# Main.net
KiCad netlist of a schematic drawn in Altium Designer
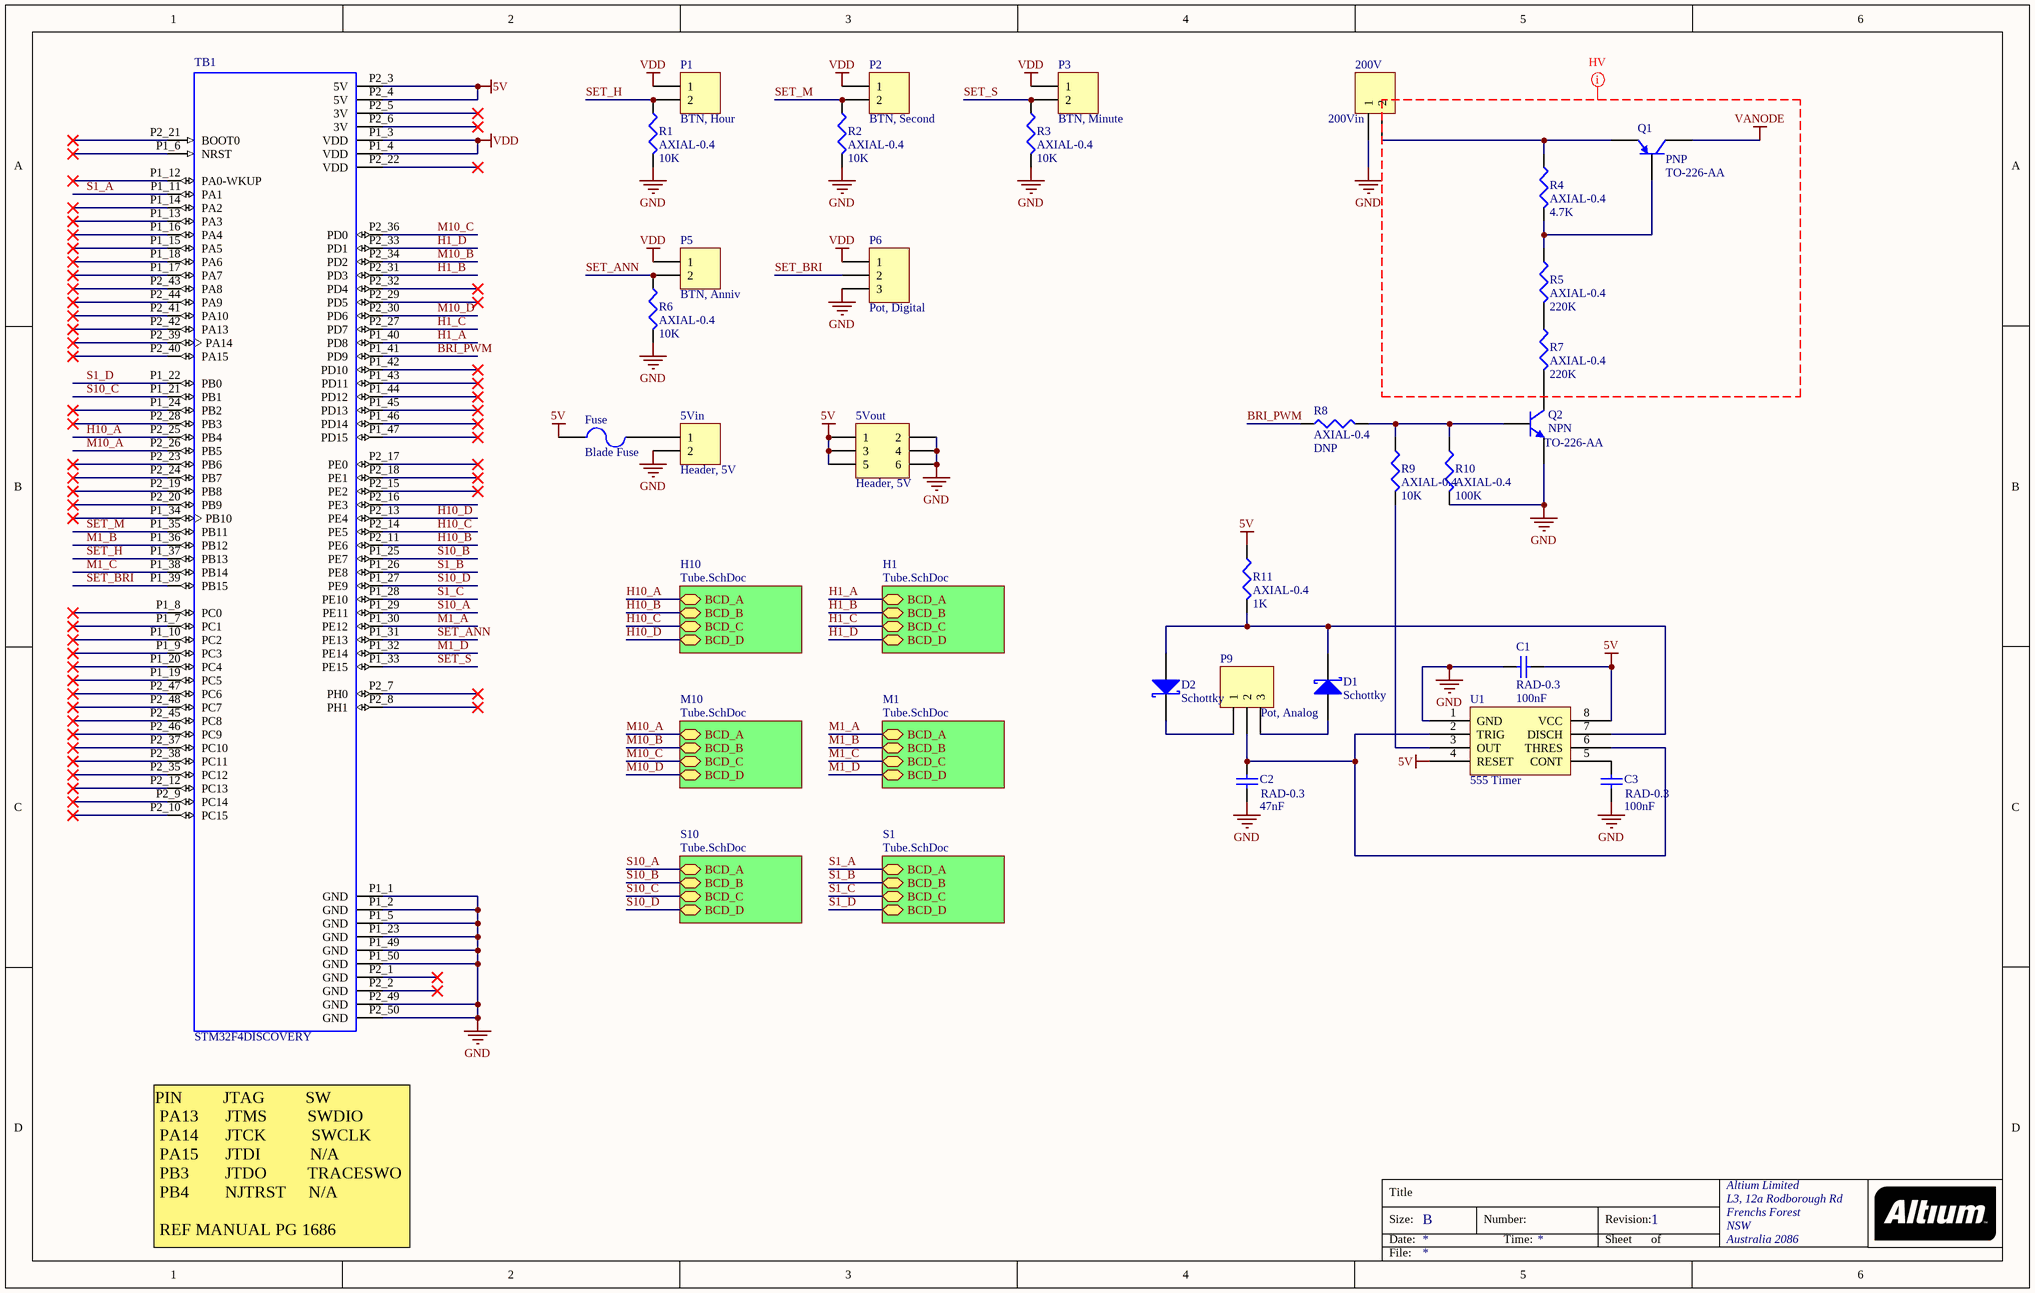
[diagram p0: Main.SchDoc]

(export (version "E")
  (design (tool "Eeschema 10.0.6"))
  (components
    (comp (ref "5Vin")
      (value "Header, 5V")
      (footprint "HDR1X2")
      (description "Header, 2-Pin")
      (fields (field (name "PUBLISHER") "Altium Limited"))
      (libsource (lib "Miscellaneous Connectors") (part "Header 2"))
    )
    (comp (ref "5Vout")
      (value "Header, 5V")
      (footprint "HDR2X3")
      (description "Header, 3-Pin, Dual row")
      (fields (field (name "PUBLISHER") "Altium Limited"))
      (libsource (lib "Miscellaneous Connectors") (part "Header 3X2"))
    )
    (comp (ref "200V")
      (value "200Vin")
      (footprint "HDR1X2H")
      (description "Header, 2-Pin, Right Angle")
      (fields (field (name "PUBLISHER") "Altium Limited"))
      (libsource (lib "Miscellaneous Connectors") (part "Header 2H"))
    )
    (comp (ref "C1")
      (value "100nF")
      (footprint "RAD-0.3")
      (description "Capacitor")
      (fields
        (field (name "PACKAGEREFERENCE") "RAD-0.3")
        (field (name "Comment") "Cap")
        (field (name "PUBLISHER") "Altium Limited")
      )
      (libsource (lib "Miscellaneous Devices") (part "Cap"))
    )
    (comp (ref "C2")
      (value "47nF")
      (footprint "RAD-0.3")
      (description "Capacitor")
      (fields (field (name "PACKAGEREFERENCE") "RAD-0.3") (field (name "PUBLISHER") "Altium Limited"))
      (libsource (lib "Miscellaneous Devices") (part "Cap"))
    )
    (comp (ref "C3")
      (value "100nF")
      (footprint "RAD-0.3")
      (description "Capacitor")
      (fields
        (field (name "PACKAGEREFERENCE") "RAD-0.3")
        (field (name "Comment") "Cap")
        (field (name "PUBLISHER") "Altium Limited")
      )
      (libsource (lib "Miscellaneous Devices") (part "Cap"))
    )
    (comp (ref "D1")
      (value "Schottky")
      (footprint "AXIAL-0.4")
      (description "Schottky Diode")
      (fields (field (name "PUBLISHER") "Altium Limited"))
      (libsource (lib "Miscellaneous Devices") (part "D Schottky"))
    )
    (comp (ref "D2")
      (value "Schottky")
      (footprint "AXIAL-0.4")
      (description "Schottky Diode")
      (fields (field (name "PUBLISHER") "Altium Limited"))
      (libsource (lib "Miscellaneous Devices") (part "D Schottky"))
    )
    (comp (ref "Fuse")
      (value "Blade Fuse")
      (footprint "FUSEHOLDER")
      (description "Fuse")
      (fields (field (name "PUBLISHER") "Altium Limited"))
      (libsource (lib "Miscellaneous Devices") (part "Fuse 2"))
    )
    (comp (ref "P1")
      (value "BTN, Hour")
      (footprint "HDR1X2")
      (description "Header, 2-Pin")
      (fields (field (name "PUBLISHER") "Altium Limited"))
      (libsource (lib "Miscellaneous Connectors") (part "Header 2"))
    )
    (comp (ref "P2")
      (value "BTN, Second")
      (footprint "HDR1X2")
      (description "Header, 2-Pin")
      (fields (field (name "PUBLISHER") "Altium Limited"))
      (libsource (lib "Miscellaneous Connectors") (part "Header 2"))
    )
    (comp (ref "P3")
      (value "BTN, Minute")
      (footprint "HDR1X2")
      (description "Header, 2-Pin")
      (fields (field (name "PUBLISHER") "Altium Limited"))
      (libsource (lib "Miscellaneous Connectors") (part "Header 2"))
    )
    (comp (ref "P5")
      (value "BTN, Anniv")
      (footprint "HDR1X2")
      (description "Header, 2-Pin")
      (fields (field (name "PUBLISHER") "Altium Limited"))
      (libsource (lib "Miscellaneous Connectors") (part "Header 2"))
    )
    (comp (ref "P6")
      (value "Pot, Digital")
      (footprint "HDR1X3")
      (description "Header, 3-Pin")
      (fields (field (name "PUBLISHER") "Altium Limited"))
      (libsource (lib "") (part "Header 3_1"))
    )
    (comp (ref "P9")
      (value "Pot, Analog")
      (footprint "HDR1X3")
      (description "Header, 3-Pin")
      (fields (field (name "PUBLISHER") "Altium Limited"))
      (libsource (lib "Miscellaneous Connectors") (part "Header 3"))
    )
    (comp (ref "Q1")
      (value "PNP")
      (footprint "T0-226-BEND")
      (description "PNP Bipolar Transistor")
      (fields (field (name "PACKAGEREFERENCE") "TO-226-AA") (field (name "PUBLISHER") "Altium Limited"))
      (libsource (lib "Miscellaneous Devices") (part "PNP"))
    )
    (comp (ref "Q2")
      (value "NPN")
      (footprint "T0-226-BEND")
      (description "NPN Bipolar Transistor")
      (fields (field (name "PACKAGEREFERENCE") "TO-226-AA") (field (name "PUBLISHER") "Altium Limited"))
      (libsource (lib "Miscellaneous Devices") (part "NPN"))
    )
    (comp (ref "R1")
      (value "AXIAL-0.4")
      (footprint "AXIAL-0.4")
      (description "Resistor")
      (fields (field (name "ALTIUM_VALUE") "10K") (field (name "PUBLISHER") "Altium Limited"))
      (libsource (lib "Miscellaneous Devices") (part "Res3"))
    )
    (comp (ref "R2")
      (value "AXIAL-0.4")
      (footprint "AXIAL-0.4")
      (description "Resistor")
      (fields (field (name "ALTIUM_VALUE") "10K") (field (name "PUBLISHER") "Altium Limited"))
      (libsource (lib "Miscellaneous Devices") (part "Res3"))
    )
    (comp (ref "R3")
      (value "AXIAL-0.4")
      (footprint "AXIAL-0.4")
      (description "Resistor")
      (fields (field (name "ALTIUM_VALUE") "10K") (field (name "PUBLISHER") "Altium Limited"))
      (libsource (lib "Miscellaneous Devices") (part "Res3"))
    )
    (comp (ref "R4")
      (value "AXIAL-0.4")
      (footprint "AXIAL-0.4")
      (description "Resistor")
      (fields (field (name "ALTIUM_VALUE") "4.7K") (field (name "PUBLISHER") "Altium Limited"))
      (libsource (lib "Miscellaneous Devices") (part "Res3"))
    )
    (comp (ref "R5")
      (value "AXIAL-0.4")
      (footprint "AXIAL-0.4")
      (description "Resistor")
      (fields (field (name "ALTIUM_VALUE") "220K") (field (name "PUBLISHER") "Altium Limited"))
      (libsource (lib "Miscellaneous Devices") (part "Res3"))
    )
    (comp (ref "R6")
      (value "AXIAL-0.4")
      (footprint "AXIAL-0.4")
      (description "Resistor")
      (fields (field (name "ALTIUM_VALUE") "10K") (field (name "PUBLISHER") "Altium Limited"))
      (libsource (lib "Miscellaneous Devices") (part "Res3"))
    )
    (comp (ref "R7")
      (value "AXIAL-0.4")
      (footprint "AXIAL-0.4")
      (description "Resistor")
      (fields (field (name "ALTIUM_VALUE") "220K") (field (name "PUBLISHER") "Altium Limited"))
      (libsource (lib "Miscellaneous Devices") (part "Res3"))
    )
    (comp (ref "R8")
      (value "AXIAL-0.4")
      (footprint "AXIAL-0.4")
      (description "Resistor")
      (fields (field (name "ALTIUM_VALUE") "DNP") (field (name "PUBLISHER") "Altium Limited"))
      (libsource (lib "Miscellaneous Devices") (part "Res3"))
    )
    (comp (ref "R9")
      (value "AXIAL-0.4")
      (footprint "AXIAL-0.4")
      (description "Resistor")
      (fields (field (name "ALTIUM_VALUE") "10K") (field (name "PUBLISHER") "Altium Limited"))
      (libsource (lib "Miscellaneous Devices") (part "Res3"))
    )
    (comp (ref "R10")
      (value "AXIAL-0.4")
      (footprint "AXIAL-0.4")
      (description "Resistor")
      (fields (field (name "ALTIUM_VALUE") "100K") (field (name "PUBLISHER") "Altium Limited"))
      (libsource (lib "Miscellaneous Devices") (part "Res3"))
    )
    (comp (ref "R11")
      (value "AXIAL-0.4")
      (footprint "AXIAL-0.4")
      (description "Resistor")
      (fields (field (name "ALTIUM_VALUE") "1K") (field (name "PUBLISHER") "Altium Limited"))
      (libsource (lib "Miscellaneous Devices") (part "Res3"))
    )
    (comp (ref "TB1")
      (value "STM32F4DISCOVERY")
      (footprint "*MODULE_STM32F4DISCOVERY_STM32F4DISCOVERY_Primary")
      (description "Development kit: ARM ST; pin strips, pin header; No.of")
      (fields (field (name "MF") "STMicroelectronics"))
      (libsource (lib "STM32F4DISCOVERY") (part "STM32F4DISCOVERY"))
    )
    (comp (ref "U1")
      (value "555 Timer")
      (footprint "DIP-8")
      (fields (field (name "PARTNUMBER") "NE555P"))
      (libsource (lib "Schematic_Components") (part "555 Timer"))
    )
  )
  (nets
    (net (code "1") (name "/BRI_PWM") (class "Default")
      (node (ref "R8") (pin "1") (pinfunction "1_1") (pintype "passive"))
      (node (ref "TB1") (pin "P1_41") (pinfunction "PD9_P1_41") (pintype "bidirectional"))
    )
    (net (code "2") (name "/H1_A") (class "Default")
      (node (ref "TB1") (pin "P1_40") (pinfunction "PD8_P1_40") (pintype "bidirectional"))
    )
    (net (code "3") (name "/H1_B") (class "Default")
      (node (ref "TB1") (pin "P2_31") (pinfunction "PD3_P2_31") (pintype "bidirectional"))
    )
    (net (code "4") (name "/H1_C") (class "Default")
      (node (ref "TB1") (pin "P2_27") (pinfunction "PD7_P2_27") (pintype "bidirectional"))
    )
    (net (code "5") (name "/H1_D") (class "Default")
      (node (ref "TB1") (pin "P2_33") (pinfunction "PD1_P2_33") (pintype "bidirectional"))
    )
    (net (code "6") (name "/H10_A") (class "Default")
      (node (ref "TB1") (pin "P2_25") (pinfunction "PB4_P2_25") (pintype "bidirectional"))
    )
    (net (code "7") (name "/H10_B") (class "Default")
      (node (ref "TB1") (pin "P2_11") (pinfunction "PE6_P2_11") (pintype "bidirectional"))
    )
    (net (code "8") (name "/H10_C") (class "Default")
      (node (ref "TB1") (pin "P2_14") (pinfunction "PE5_P2_14") (pintype "bidirectional"))
    )
    (net (code "9") (name "/H10_D") (class "Default")
      (node (ref "TB1") (pin "P2_13") (pinfunction "PE4_P2_13") (pintype "bidirectional"))
    )
    (net (code "10") (name "/M1_A") (class "Default")
      (node (ref "TB1") (pin "P1_30") (pinfunction "PE12_P1_30") (pintype "bidirectional"))
    )
    (net (code "11") (name "/M1_B") (class "Default")
      (node (ref "TB1") (pin "P1_36") (pinfunction "PB12_P1_36") (pintype "bidirectional"))
    )
    (net (code "12") (name "/M1_C") (class "Default")
      (node (ref "TB1") (pin "P1_38") (pinfunction "PB14_P1_38") (pintype "bidirectional"))
    )
    (net (code "13") (name "/M1_D") (class "Default")
      (node (ref "TB1") (pin "P1_32") (pinfunction "PE14_P1_32") (pintype "bidirectional"))
    )
    (net (code "14") (name "/M10_A") (class "Default")
      (node (ref "TB1") (pin "P2_26") (pinfunction "PB5_P2_26") (pintype "bidirectional"))
    )
    (net (code "15") (name "/M10_B") (class "Default")
      (node (ref "TB1") (pin "P2_34") (pinfunction "PD2_P2_34") (pintype "bidirectional"))
    )
    (net (code "16") (name "/M10_C") (class "Default")
      (node (ref "TB1") (pin "P2_36") (pinfunction "PD0_P2_36") (pintype "bidirectional"))
    )
    (net (code "17") (name "/M10_D") (class "Default")
      (node (ref "TB1") (pin "P2_30") (pinfunction "PD6_P2_30") (pintype "bidirectional"))
    )
    (net (code "18") (name "/S1_A") (class "Default")
      (node (ref "TB1") (pin "P1_11") (pinfunction "PA1_P1_11") (pintype "bidirectional"))
    )
    (net (code "19") (name "/S1_B") (class "Default")
      (node (ref "TB1") (pin "P1_26") (pinfunction "PE8_P1_26") (pintype "bidirectional"))
    )
    (net (code "20") (name "/S1_C") (class "Default")
      (node (ref "TB1") (pin "P1_28") (pinfunction "PE10_P1_28") (pintype "bidirectional"))
    )
    (net (code "21") (name "/S1_D") (class "Default")
      (node (ref "TB1") (pin "P1_22") (pinfunction "PB0_P1_22") (pintype "bidirectional"))
    )
    (net (code "22") (name "/S10_A") (class "Default")
      (node (ref "TB1") (pin "P1_29") (pinfunction "PE11_P1_29") (pintype "bidirectional"))
    )
    (net (code "23") (name "/S10_B") (class "Default")
      (node (ref "TB1") (pin "P1_25") (pinfunction "PE7_P1_25") (pintype "bidirectional"))
    )
    (net (code "24") (name "/S10_C") (class "Default")
      (node (ref "TB1") (pin "P1_21") (pinfunction "PB1_P1_21") (pintype "bidirectional"))
    )
    (net (code "25") (name "/S10_D") (class "Default")
      (node (ref "TB1") (pin "P1_27") (pinfunction "PE9_P1_27") (pintype "bidirectional"))
    )
    (net (code "26") (name "/SET_ANN") (class "Default")
      (node (ref "P5") (pin "2") (pinfunction "2_2") (pintype "passive"))
      (node (ref "R6") (pin "1") (pinfunction "1_1") (pintype "passive"))
      (node (ref "TB1") (pin "P1_31") (pinfunction "PE13_P1_31") (pintype "bidirectional"))
    )
    (net (code "27") (name "/SET_BRI") (class "Default")
      (node (ref "P6") (pin "2") (pinfunction "2_2") (pintype "passive"))
      (node (ref "TB1") (pin "P1_39") (pinfunction "PB15_P1_39") (pintype "bidirectional"))
    )
    (net (code "28") (name "/SET_H") (class "Default")
      (node (ref "P1") (pin "2") (pinfunction "2_2") (pintype "passive"))
      (node (ref "R1") (pin "1") (pinfunction "1_1") (pintype "passive"))
      (node (ref "TB1") (pin "P1_37") (pinfunction "PB13_P1_37") (pintype "bidirectional"))
    )
    (net (code "29") (name "/SET_M") (class "Default")
      (node (ref "P2") (pin "2") (pinfunction "2_2") (pintype "passive"))
      (node (ref "R2") (pin "1") (pinfunction "1_1") (pintype "passive"))
      (node (ref "TB1") (pin "P1_35") (pinfunction "PB11_P1_35") (pintype "bidirectional"))
    )
    (net (code "30") (name "/SET_S") (class "Default")
      (node (ref "P3") (pin "2") (pinfunction "2_2") (pintype "passive"))
      (node (ref "R3") (pin "1") (pinfunction "1_1") (pintype "passive"))
      (node (ref "TB1") (pin "P1_33") (pinfunction "PE15_P1_33") (pintype "bidirectional"))
    )
    (net (code "31") (name "5V") (class "Default")
      (node (ref "5Vout") (pin "1") (pinfunction "1_1") (pintype "passive"))
      (node (ref "5Vout") (pin "3") (pinfunction "3_3") (pintype "passive"))
      (node (ref "5Vout") (pin "5") (pinfunction "5_5") (pintype "passive"))
      (node (ref "C1") (pin "1") (pinfunction "1_1") (pintype "passive"))
      (node (ref "Fuse") (pin "2") (pinfunction "2_2") (pintype "passive"))
      (node (ref "R11") (pin "1") (pinfunction "1_1") (pintype "passive"))
      (node (ref "TB1") (pin "P2_3") (pinfunction "5V_P2_3") (pintype "power_in"))
      (node (ref "TB1") (pin "P2_4") (pinfunction "5V_P2_4") (pintype "power_in"))
      (node (ref "U1") (pin "4") (pinfunction "RESET_4") (pintype "passive"))
      (node (ref "U1") (pin "8") (pinfunction "VCC_8") (pintype "passive"))
    )
    (net (code "32") (name "GND") (class "Default")
      (node (ref "200V") (pin "1") (pinfunction "1_1") (pintype "passive"))
      (node (ref "5Vin") (pin "2") (pinfunction "2_2") (pintype "passive"))
      (node (ref "5Vout") (pin "2") (pinfunction "2_2") (pintype "passive"))
      (node (ref "5Vout") (pin "4") (pinfunction "4_4") (pintype "passive"))
      (node (ref "5Vout") (pin "6") (pinfunction "6_6") (pintype "passive"))
      (node (ref "C1") (pin "2") (pinfunction "2_2") (pintype "passive"))
      (node (ref "C2") (pin "1") (pinfunction "1_1") (pintype "passive"))
      (node (ref "C3") (pin "1") (pinfunction "1_1") (pintype "passive"))
      (node (ref "P6") (pin "3") (pinfunction "3_3") (pintype "passive"))
      (node (ref "Q2") (pin "3") (pinfunction "E_3") (pintype "passive"))
      (node (ref "R1") (pin "2") (pinfunction "2_2") (pintype "passive"))
      (node (ref "R10") (pin "2") (pinfunction "2_2") (pintype "passive"))
      (node (ref "R2") (pin "2") (pinfunction "2_2") (pintype "passive"))
      (node (ref "R3") (pin "2") (pinfunction "2_2") (pintype "passive"))
      (node (ref "R6") (pin "2") (pinfunction "2_2") (pintype "passive"))
      (node (ref "TB1") (pin "P1_1") (pinfunction "GND_P1_1") (pintype "power_in"))
      (node (ref "TB1") (pin "P1_2") (pinfunction "GND_P1_2") (pintype "power_in"))
      (node (ref "TB1") (pin "P1_23") (pinfunction "GND_P1_23") (pintype "power_in"))
      (node (ref "TB1") (pin "P1_49") (pinfunction "GND_P1_49") (pintype "power_in"))
      (node (ref "TB1") (pin "P1_5") (pinfunction "GND_P1_5") (pintype "power_in"))
      (node (ref "TB1") (pin "P1_50") (pinfunction "GND_P1_50") (pintype "power_in"))
      (node (ref "TB1") (pin "P2_49") (pinfunction "GND_P2_49") (pintype "power_in"))
      (node (ref "TB1") (pin "P2_50") (pinfunction "GND_P2_50") (pintype "power_in"))
      (node (ref "U1") (pin "1") (pinfunction "GND_1") (pintype "passive"))
    )
    (net (code "33") (name "Net-(5Vin-Pad1)") (class "Default")
      (node (ref "5Vin") (pin "1") (pinfunction "1_1") (pintype "passive"))
      (node (ref "Fuse") (pin "1") (pinfunction "1_1") (pintype "passive"))
    )
    (net (code "34") (name "Net-(D1-A)") (class "Default")
      (node (ref "D1") (pin "1") (pinfunction "A_1") (pintype "passive"))
      (node (ref "P9") (pin "3") (pinfunction "3_3") (pintype "passive"))
    )
    (net (code "35") (name "Net-(D1-K)") (class "Default")
      (node (ref "D1") (pin "2") (pinfunction "K_2") (pintype "passive"))
      (node (ref "D2") (pin "1") (pinfunction "A_1") (pintype "passive"))
      (node (ref "R11") (pin "2") (pinfunction "2_2") (pintype "passive"))
      (node (ref "U1") (pin "7") (pinfunction "DISCH_7") (pintype "passive"))
    )
    (net (code "36") (name "Net-(D2-K)") (class "Default")
      (node (ref "D2") (pin "2") (pinfunction "K_2") (pintype "passive"))
      (node (ref "P9") (pin "1") (pinfunction "1_1") (pintype "passive"))
    )
    (net (code "37") (name "Net-(Q1-B)") (class "Default")
      (node (ref "Q1") (pin "2") (pinfunction "B_2") (pintype "passive"))
      (node (ref "R4") (pin "2") (pinfunction "2_2") (pintype "passive"))
      (node (ref "R5") (pin "1") (pinfunction "1_1") (pintype "passive"))
    )
    (net (code "38") (name "Net-(Q1-E)") (class "Default")
      (node (ref "200V") (pin "2") (pinfunction "2_2") (pintype "passive"))
      (node (ref "Q1") (pin "3") (pinfunction "E_3") (pintype "passive"))
      (node (ref "R4") (pin "1") (pinfunction "1_1") (pintype "passive"))
    )
    (net (code "39") (name "Net-(Q2-B)") (class "Default")
      (node (ref "Q2") (pin "2") (pinfunction "B_2") (pintype "passive"))
      (node (ref "R10") (pin "1") (pinfunction "1_1") (pintype "passive"))
      (node (ref "R8") (pin "2") (pinfunction "2_2") (pintype "passive"))
      (node (ref "R9") (pin "1") (pinfunction "1_1") (pintype "passive"))
    )
    (net (code "40") (name "Net-(Q2-C)") (class "Default")
      (node (ref "Q2") (pin "1") (pinfunction "C_1") (pintype "passive"))
      (node (ref "R7") (pin "2") (pinfunction "2_2") (pintype "passive"))
    )
    (net (code "41") (name "Net-(R5-Pad2)") (class "Default")
      (node (ref "R5") (pin "2") (pinfunction "2_2") (pintype "passive"))
      (node (ref "R7") (pin "1") (pinfunction "1_1") (pintype "passive"))
    )
    (net (code "42") (name "Net-(U1-CONT)") (class "Default")
      (node (ref "C3") (pin "2") (pinfunction "2_2") (pintype "passive"))
      (node (ref "U1") (pin "5") (pinfunction "CONT_5") (pintype "passive"))
    )
    (net (code "43") (name "Net-(U1-OUT)") (class "Default")
      (node (ref "R9") (pin "2") (pinfunction "2_2") (pintype "passive"))
      (node (ref "U1") (pin "3") (pinfunction "OUT_3") (pintype "passive"))
    )
    (net (code "44") (name "Net-(U1-THRES)") (class "Default")
      (node (ref "C2") (pin "2") (pinfunction "2_2") (pintype "passive"))
      (node (ref "P9") (pin "2") (pinfunction "2_2") (pintype "passive"))
      (node (ref "U1") (pin "2") (pinfunction "TRIG_2") (pintype "passive"))
      (node (ref "U1") (pin "6") (pinfunction "THRES_6") (pintype "passive"))
    )
    (net (code "45") (name "VANODE") (class "Default")
      (node (ref "Q1") (pin "1") (pinfunction "C_1") (pintype "passive"))
    )
    (net (code "46") (name "VDD") (class "Default")
      (node (ref "P1") (pin "1") (pinfunction "1_1") (pintype "passive"))
      (node (ref "P2") (pin "1") (pinfunction "1_1") (pintype "passive"))
      (node (ref "P3") (pin "1") (pinfunction "1_1") (pintype "passive"))
      (node (ref "P5") (pin "1") (pinfunction "1_1") (pintype "passive"))
      (node (ref "P6") (pin "1") (pinfunction "1_1") (pintype "passive"))
      (node (ref "TB1") (pin "P1_3") (pinfunction "VDD_P1_3") (pintype "power_in"))
      (node (ref "TB1") (pin "P1_4") (pinfunction "VDD_P1_4") (pintype "power_in"))
    )
    (net (code "47") (name "unconnected-(TB1-3V-PadP2_5)") (class "Default")
      (node (ref "TB1") (pin "P2_5") (pinfunction "3V_P2_5") (pintype "power_in+no_connect"))
    )
    (net (code "48") (name "unconnected-(TB1-3V-PadP2_6)") (class "Default")
      (node (ref "TB1") (pin "P2_6") (pinfunction "3V_P2_6") (pintype "power_in+no_connect"))
    )
    (net (code "49") (name "unconnected-(TB1-BOOT0-PadP2_21)") (class "Default")
      (node (ref "TB1") (pin "P2_21") (pinfunction "BOOT0_P2_21") (pintype "input+no_connect"))
    )
    (net (code "50") (name "unconnected-(TB1-GND-PadP2_1)") (class "Default")
      (node (ref "TB1") (pin "P2_1") (pinfunction "GND_P2_1") (pintype "power_in+no_connect"))
    )
    (net (code "51") (name "unconnected-(TB1-GND-PadP2_2)") (class "Default")
      (node (ref "TB1") (pin "P2_2") (pinfunction "GND_P2_2") (pintype "power_in+no_connect"))
    )
    (net (code "52") (name "unconnected-(TB1-NRST-PadP1_6)") (class "Default")
      (node (ref "TB1") (pin "P1_6") (pinfunction "NRST_P1_6") (pintype "input+no_connect"))
    )
    (net (code "53") (name "unconnected-(TB1-PA0-WKUP-PadP1_12)") (class "Default")
      (node (ref "TB1") (pin "P1_12") (pinfunction "PA0-WKUP_P1_12") (pintype "bidirectional+no_connect"))
    )
    (net (code "54") (name "unconnected-(TB1-PA2-PadP1_14)") (class "Default")
      (node (ref "TB1") (pin "P1_14") (pinfunction "PA2_P1_14") (pintype "bidirectional+no_connect"))
    )
    (net (code "55") (name "unconnected-(TB1-PA3-PadP1_13)") (class "Default")
      (node (ref "TB1") (pin "P1_13") (pinfunction "PA3_P1_13") (pintype "bidirectional+no_connect"))
    )
    (net (code "56") (name "unconnected-(TB1-PA4-PadP1_16)") (class "Default")
      (node (ref "TB1") (pin "P1_16") (pinfunction "PA4_P1_16") (pintype "bidirectional+no_connect"))
    )
    (net (code "57") (name "unconnected-(TB1-PA5-PadP1_15)") (class "Default")
      (node (ref "TB1") (pin "P1_15") (pinfunction "PA5_P1_15") (pintype "bidirectional+no_connect"))
    )
    (net (code "58") (name "unconnected-(TB1-PA6-PadP1_18)") (class "Default")
      (node (ref "TB1") (pin "P1_18") (pinfunction "PA6_P1_18") (pintype "bidirectional+no_connect"))
    )
    (net (code "59") (name "unconnected-(TB1-PA7-PadP1_17)") (class "Default")
      (node (ref "TB1") (pin "P1_17") (pinfunction "PA7_P1_17") (pintype "bidirectional+no_connect"))
    )
    (net (code "60") (name "unconnected-(TB1-PA8-PadP2_43)") (class "Default")
      (node (ref "TB1") (pin "P2_43") (pinfunction "PA8_P2_43") (pintype "bidirectional+no_connect"))
    )
    (net (code "61") (name "unconnected-(TB1-PA9-PadP2_44)") (class "Default")
      (node (ref "TB1") (pin "P2_44") (pinfunction "PA9_P2_44") (pintype "bidirectional+no_connect"))
    )
    (net (code "62") (name "unconnected-(TB1-PA10-PadP2_41)") (class "Default")
      (node (ref "TB1") (pin "P2_41") (pinfunction "PA10_P2_41") (pintype "bidirectional+no_connect"))
    )
    (net (code "63") (name "unconnected-(TB1-PA13-PadP2_42)") (class "Default")
      (node (ref "TB1") (pin "P2_42") (pinfunction "PA13_P2_42") (pintype "bidirectional+no_connect"))
    )
    (net (code "64") (name "unconnected-(TB1-PA14-PadP2_39)") (class "Default")
      (node (ref "TB1") (pin "P2_39") (pinfunction "PA14_P2_39") (pintype "bidirectional+no_connect"))
    )
    (net (code "65") (name "unconnected-(TB1-PA15-PadP2_40)") (class "Default")
      (node (ref "TB1") (pin "P2_40") (pinfunction "PA15_P2_40") (pintype "bidirectional+no_connect"))
    )
    (net (code "66") (name "unconnected-(TB1-PB2-PadP1_24)") (class "Default")
      (node (ref "TB1") (pin "P1_24") (pinfunction "PB2_P1_24") (pintype "bidirectional+no_connect"))
    )
    (net (code "67") (name "unconnected-(TB1-PB3-PadP2_28)") (class "Default")
      (node (ref "TB1") (pin "P2_28") (pinfunction "PB3_P2_28") (pintype "bidirectional+no_connect"))
    )
    (net (code "68") (name "unconnected-(TB1-PB6-PadP2_23)") (class "Default")
      (node (ref "TB1") (pin "P2_23") (pinfunction "PB6_P2_23") (pintype "bidirectional+no_connect"))
    )
    (net (code "69") (name "unconnected-(TB1-PB7-PadP2_24)") (class "Default")
      (node (ref "TB1") (pin "P2_24") (pinfunction "PB7_P2_24") (pintype "bidirectional+no_connect"))
    )
    (net (code "70") (name "unconnected-(TB1-PB8-PadP2_19)") (class "Default")
      (node (ref "TB1") (pin "P2_19") (pinfunction "PB8_P2_19") (pintype "bidirectional+no_connect"))
    )
    (net (code "71") (name "unconnected-(TB1-PB9-PadP2_20)") (class "Default")
      (node (ref "TB1") (pin "P2_20") (pinfunction "PB9_P2_20") (pintype "bidirectional+no_connect"))
    )
    (net (code "72") (name "unconnected-(TB1-PB10-PadP1_34)") (class "Default")
      (node (ref "TB1") (pin "P1_34") (pinfunction "PB10_P1_34") (pintype "bidirectional+no_connect"))
    )
    (net (code "73") (name "unconnected-(TB1-PC0-PadP1_8)") (class "Default")
      (node (ref "TB1") (pin "P1_8") (pinfunction "PC0_P1_8") (pintype "bidirectional+no_connect"))
    )
    (net (code "74") (name "unconnected-(TB1-PC1-PadP1_7)") (class "Default")
      (node (ref "TB1") (pin "P1_7") (pinfunction "PC1_P1_7") (pintype "bidirectional+no_connect"))
    )
    (net (code "75") (name "unconnected-(TB1-PC2-PadP1_10)") (class "Default")
      (node (ref "TB1") (pin "P1_10") (pinfunction "PC2_P1_10") (pintype "bidirectional+no_connect"))
    )
    (net (code "76") (name "unconnected-(TB1-PC3-PadP1_9)") (class "Default")
      (node (ref "TB1") (pin "P1_9") (pinfunction "PC3_P1_9") (pintype "bidirectional+no_connect"))
    )
    (net (code "77") (name "unconnected-(TB1-PC4-PadP1_20)") (class "Default")
      (node (ref "TB1") (pin "P1_20") (pinfunction "PC4_P1_20") (pintype "bidirectional+no_connect"))
    )
    (net (code "78") (name "unconnected-(TB1-PC5-PadP1_19)") (class "Default")
      (node (ref "TB1") (pin "P1_19") (pinfunction "PC5_P1_19") (pintype "bidirectional+no_connect"))
    )
    (net (code "79") (name "unconnected-(TB1-PC6-PadP2_47)") (class "Default")
      (node (ref "TB1") (pin "P2_47") (pinfunction "PC6_P2_47") (pintype "bidirectional+no_connect"))
    )
    (net (code "80") (name "unconnected-(TB1-PC7-PadP2_48)") (class "Default")
      (node (ref "TB1") (pin "P2_48") (pinfunction "PC7_P2_48") (pintype "bidirectional+no_connect"))
    )
    (net (code "81") (name "unconnected-(TB1-PC8-PadP2_45)") (class "Default")
      (node (ref "TB1") (pin "P2_45") (pinfunction "PC8_P2_45") (pintype "bidirectional+no_connect"))
    )
    (net (code "82") (name "unconnected-(TB1-PC9-PadP2_46)") (class "Default")
      (node (ref "TB1") (pin "P2_46") (pinfunction "PC9_P2_46") (pintype "bidirectional+no_connect"))
    )
    (net (code "83") (name "unconnected-(TB1-PC10-PadP2_37)") (class "Default")
      (node (ref "TB1") (pin "P2_37") (pinfunction "PC10_P2_37") (pintype "bidirectional+no_connect"))
    )
    (net (code "84") (name "unconnected-(TB1-PC11-PadP2_38)") (class "Default")
      (node (ref "TB1") (pin "P2_38") (pinfunction "PC11_P2_38") (pintype "bidirectional+no_connect"))
    )
    (net (code "85") (name "unconnected-(TB1-PC12-PadP2_35)") (class "Default")
      (node (ref "TB1") (pin "P2_35") (pinfunction "PC12_P2_35") (pintype "bidirectional+no_connect"))
    )
    (net (code "86") (name "unconnected-(TB1-PC13-PadP2_12)") (class "Default")
      (node (ref "TB1") (pin "P2_12") (pinfunction "PC13_P2_12") (pintype "bidirectional+no_connect"))
    )
    (net (code "87") (name "unconnected-(TB1-PC14-PadP2_9)") (class "Default")
      (node (ref "TB1") (pin "P2_9") (pinfunction "PC14_P2_9") (pintype "bidirectional+no_connect"))
    )
    (net (code "88") (name "unconnected-(TB1-PC15-PadP2_10)") (class "Default")
      (node (ref "TB1") (pin "P2_10") (pinfunction "PC15_P2_10") (pintype "bidirectional+no_connect"))
    )
    (net (code "89") (name "unconnected-(TB1-PD4-PadP2_32)") (class "Default")
      (node (ref "TB1") (pin "P2_32") (pinfunction "PD4_P2_32") (pintype "bidirectional+no_connect"))
    )
    (net (code "90") (name "unconnected-(TB1-PD5-PadP2_29)") (class "Default")
      (node (ref "TB1") (pin "P2_29") (pinfunction "PD5_P2_29") (pintype "bidirectional+no_connect"))
    )
    (net (code "91") (name "unconnected-(TB1-PD10-PadP1_42)") (class "Default")
      (node (ref "TB1") (pin "P1_42") (pinfunction "PD10_P1_42") (pintype "bidirectional+no_connect"))
    )
    (net (code "92") (name "unconnected-(TB1-PD11-PadP1_43)") (class "Default")
      (node (ref "TB1") (pin "P1_43") (pinfunction "PD11_P1_43") (pintype "bidirectional+no_connect"))
    )
    (net (code "93") (name "unconnected-(TB1-PD12-PadP1_44)") (class "Default")
      (node (ref "TB1") (pin "P1_44") (pinfunction "PD12_P1_44") (pintype "bidirectional+no_connect"))
    )
    (net (code "94") (name "unconnected-(TB1-PD13-PadP1_45)") (class "Default")
      (node (ref "TB1") (pin "P1_45") (pinfunction "PD13_P1_45") (pintype "bidirectional+no_connect"))
    )
    (net (code "95") (name "unconnected-(TB1-PD14-PadP1_46)") (class "Default")
      (node (ref "TB1") (pin "P1_46") (pinfunction "PD14_P1_46") (pintype "bidirectional+no_connect"))
    )
    (net (code "96") (name "unconnected-(TB1-PD15-PadP1_47)") (class "Default")
      (node (ref "TB1") (pin "P1_47") (pinfunction "PD15_P1_47") (pintype "bidirectional+no_connect"))
    )
    (net (code "97") (name "unconnected-(TB1-PE0-PadP2_17)") (class "Default")
      (node (ref "TB1") (pin "P2_17") (pinfunction "PE0_P2_17") (pintype "bidirectional+no_connect"))
    )
    (net (code "98") (name "unconnected-(TB1-PE1-PadP2_18)") (class "Default")
      (node (ref "TB1") (pin "P2_18") (pinfunction "PE1_P2_18") (pintype "bidirectional+no_connect"))
    )
    (net (code "99") (name "unconnected-(TB1-PE2-PadP2_15)") (class "Default")
      (node (ref "TB1") (pin "P2_15") (pinfunction "PE2_P2_15") (pintype "bidirectional+no_connect"))
    )
    (net (code "100") (name "unconnected-(TB1-PE3-PadP2_16)") (class "Default")
      (node (ref "TB1") (pin "P2_16") (pinfunction "PE3_P2_16") (pintype "bidirectional"))
    )
    (net (code "101") (name "unconnected-(TB1-PH0-PadP2_7)") (class "Default")
      (node (ref "TB1") (pin "P2_7") (pinfunction "PH0_P2_7") (pintype "bidirectional+no_connect"))
    )
    (net (code "102") (name "unconnected-(TB1-PH1-PadP2_8)") (class "Default")
      (node (ref "TB1") (pin "P2_8") (pinfunction "PH1_P2_8") (pintype "bidirectional+no_connect"))
    )
    (net (code "103") (name "unconnected-(TB1-VDD-PadP2_22)") (class "Default")
      (node (ref "TB1") (pin "P2_22") (pinfunction "VDD_P2_22") (pintype "power_in+no_connect"))
    )
  )
)
